# PA_stage_2.net
KiCad netlist of a schematic drawn in Altium Designer
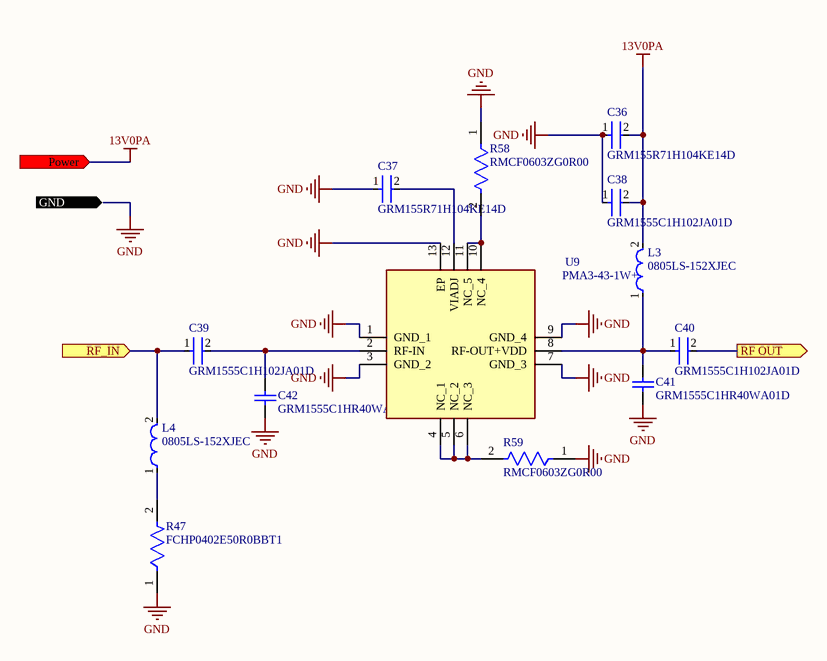
[diagram p0: PA stage 2.SchDoc]

(export (version "E")
  (design (tool "Eeschema 10.0.6"))
  (components
    (comp (ref "C36")
      (value "GRM155R71H104KE14D")
      (footprint "FP-GRM155-0_05-IPC_B")
      (description "Chip Multilayer Ceramic Capacitors for General Purpose, 0402, 0.10uF, X7R, 15%, 10%, 50V")
      (fields (field (name "VOLTAGE") "50V") (field (name "TOLERANCE") "10%"))
      (libsource (lib "Altium Content Vault") (part "02cd4be3c70576c341d710602a673aa"))
    )
    (comp (ref "C37")
      (value "GRM155R71H104KE14D")
      (footprint "FP-GRM155-0_05-IPC_B")
      (description "Chip Multilayer Ceramic Capacitors for General Purpose, 0402, 0.10uF, X7R, 15%, 10%, 50V")
      (fields (field (name "VOLTAGE") "50V") (field (name "TOLERANCE") "10%"))
      (libsource (lib "Altium Content Vault") (part "02cd4be3c70576c341d710602a673aa"))
    )
    (comp (ref "C38")
      (value "GRM1555C1H102JA01D")
      (footprint "FP-GRM155-0_05-IPC_B")
      (description "Chip Multilayer Ceramic Capacitors for General Purpose, 0402, 1000pF, C0G, 30ppm/°C, 5%, 50V")
      (fields (field (name "TOLERANCE") "5%") (field (name "VOLTAGE") "50V"))
      (libsource (lib "Altium Content Vault") (part "02cd4be3c70576c341d710602a673aa"))
    )
    (comp (ref "C39")
      (value "GRM1555C1H102JA01D")
      (footprint "FP-GRM155-0_05-IPC_B")
      (description "Chip Multilayer Ceramic Capacitors for General Purpose, 0402, 1000pF, C0G, 30ppm/°C, 5%, 50V")
      (fields (field (name "TOLERANCE") "5%") (field (name "VOLTAGE") "50V"))
      (libsource (lib "Altium Content Vault") (part "02cd4be3c70576c341d710602a673aa"))
    )
    (comp (ref "C40")
      (value "GRM1555C1H102JA01D")
      (footprint "FP-GRM155-0_05-IPC_B")
      (description "Chip Multilayer Ceramic Capacitors for General Purpose, 0402, 1000pF, C0G, 30ppm/°C, 5%, 50V")
      (fields (field (name "TOLERANCE") "5%") (field (name "VOLTAGE") "50V"))
      (libsource (lib "Altium Content Vault") (part "02cd4be3c70576c341d710602a673aa"))
    )
    (comp (ref "C41")
      (value "GRM1555C1HR40WA01D")
      (footprint "CAPC1005X55X25LL05T10")
      (fields (field (name "MANUFACTURER") "Murata"))
      (libsource (lib "Altium Content Vault") (part "CAP"))
    )
    (comp (ref "C42")
      (value "GRM1555C1HR40WA01D")
      (footprint "CAPC1005X55X25LL05T10")
      (fields (field (name "MANUFACTURER") "Murata"))
      (libsource (lib "Altium Content Vault") (part "CAP"))
    )
    (comp (ref "L3")
      (value "0805LS-152XJEC")
      (footprint "FP-LQW21HN_00-MFG")
      (description "0805LS-152XJEC Coilcraft")
      (fields (field (name "TOLERANCE") "5%"))
      (libsource (lib "Altium Content Vault") (part "725321dda6339637d4d059423bc1c3c"))
    )
    (comp (ref "L4")
      (value "0805LS-152XJEC")
      (footprint "FP-LQW21HN_00-MFG")
      (description "0805LS-152XJEC Coilcraft")
      (fields (field (name "TOLERANCE") "5%"))
      (libsource (lib "Altium Content Vault") (part "725321dda6339637d4d059423bc1c3c"))
    )
    (comp (ref "R47")
      (value "FCHP0402E50R0BBT1")
      (footprint "FP-FC0402-MFG")
      (fields (field (name "TOLERANCE") "0.1%"))
      (libsource (lib "Altium Content Vault") (part "1029c3af85768c4190bb7ad29bc67b5"))
    )
    (comp (ref "R58")
      (value "RMCF0603ZG0R00")
      (footprint "FP-RMCF0603-IPC_B")
      (description "0Ω ±0 0.1W 0603 Thick Film Chip Resistor AEC-Q200 compliant")
      (libsource (lib "Altium Content Vault") (part "1029c3af85768c4190bb7ad29bc67b5"))
    )
    (comp (ref "R59")
      (value "RMCF0603ZG0R00")
      (footprint "FP-RMCF0603-IPC_B")
      (description "0Ω ±0 0.1W 0603 Thick Film Chip Resistor AEC-Q200 compliant")
      (libsource (lib "Altium Content Vault") (part "1029c3af85768c4190bb7ad29bc67b5"))
    )
    (comp (ref "U9")
      (value "PMA3-43-1W+")
      (footprint "QFN51P300X300X89-13N")
      (description "Integrated Circuit")
      (libsource (lib "SamacSys") (part "PMA3-43-1W+"))
    )
  )
  (nets
    (net (code "1") (name "/RF OUT") (class "Default")
      (node (ref "C40") (pin "2") (pinfunction "2_2") (pintype "passive"))
    )
    (net (code "2") (name "/RF_IN") (class "Default")
      (node (ref "C39") (pin "1") (pinfunction "1_1") (pintype "passive"))
      (node (ref "L4") (pin "2") (pinfunction "2_2") (pintype "passive"))
    )
    (net (code "3") (name "13V0PA") (class "Default")
      (node (ref "C36") (pin "2") (pinfunction "2_2") (pintype "passive"))
      (node (ref "C38") (pin "2") (pinfunction "2_2") (pintype "passive"))
      (node (ref "L3") (pin "2") (pinfunction "2_2") (pintype "passive"))
    )
    (net (code "4") (name "GND") (class "Default")
      (node (ref "C36") (pin "1") (pinfunction "1_1") (pintype "passive"))
      (node (ref "C37") (pin "1") (pinfunction "1_1") (pintype "passive"))
      (node (ref "C38") (pin "1") (pinfunction "1_1") (pintype "passive"))
      (node (ref "C41") (pin "1") (pinfunction "1_1") (pintype "passive"))
      (node (ref "C42") (pin "1") (pinfunction "1_1") (pintype "passive"))
      (node (ref "R47") (pin "1") (pinfunction "1_1") (pintype "passive"))
      (node (ref "R58") (pin "1") (pinfunction "1_1") (pintype "passive"))
      (node (ref "R59") (pin "1") (pinfunction "1_1") (pintype "passive"))
      (node (ref "U9") (pin "1") (pinfunction "GND_1_1") (pintype "passive"))
      (node (ref "U9") (pin "13") (pinfunction "EP_13") (pintype "passive"))
      (node (ref "U9") (pin "3") (pinfunction "GND_2_3") (pintype "passive"))
      (node (ref "U9") (pin "7") (pinfunction "GND_3_7") (pintype "passive"))
      (node (ref "U9") (pin "9") (pinfunction "GND_4_9") (pintype "passive"))
    )
    (net (code "5") (name "Net-(L4-Pad1)") (class "Default")
      (node (ref "L4") (pin "1") (pinfunction "1_1") (pintype "passive"))
      (node (ref "R47") (pin "2") (pinfunction "2_2") (pintype "passive"))
    )
    (net (code "6") (name "Net-(U9-NC_1)") (class "Default")
      (node (ref "R59") (pin "2") (pinfunction "2_2") (pintype "passive"))
      (node (ref "U9") (pin "4") (pinfunction "NC_1_4") (pintype "passive"))
      (node (ref "U9") (pin "5") (pinfunction "NC_2_5") (pintype "passive"))
      (node (ref "U9") (pin "6") (pinfunction "NC_3_6") (pintype "passive"))
    )
    (net (code "7") (name "Net-(U9-NC_4)") (class "Default")
      (node (ref "R58") (pin "2") (pinfunction "2_2") (pintype "passive"))
      (node (ref "U9") (pin "10") (pinfunction "NC_4_10") (pintype "passive"))
      (node (ref "U9") (pin "11") (pinfunction "NC_5_11") (pintype "passive"))
    )
    (net (code "8") (name "Net-(U9-RF-IN)") (class "Default")
      (node (ref "C39") (pin "2") (pinfunction "2_2") (pintype "passive"))
      (node (ref "C42") (pin "2") (pinfunction "2_2") (pintype "passive"))
      (node (ref "U9") (pin "2") (pinfunction "RF-IN_2") (pintype "passive"))
    )
    (net (code "9") (name "Net-(U9-RF-OUT+VDD)") (class "Default")
      (node (ref "C40") (pin "1") (pinfunction "1_1") (pintype "passive"))
      (node (ref "C41") (pin "2") (pinfunction "2_2") (pintype "passive"))
      (node (ref "L3") (pin "1") (pinfunction "1_1") (pintype "passive"))
      (node (ref "U9") (pin "8") (pinfunction "RF-OUT+VDD_8") (pintype "passive"))
    )
    (net (code "10") (name "Net-(U9-VIADJ)") (class "Default")
      (node (ref "C37") (pin "2") (pinfunction "2_2") (pintype "passive"))
      (node (ref "U9") (pin "12") (pinfunction "VIADJ_12") (pintype "passive"))
    )
  )
)
